# Fastino_DAC_channel.net
KiCad netlist of a schematic drawn in Altium Designer
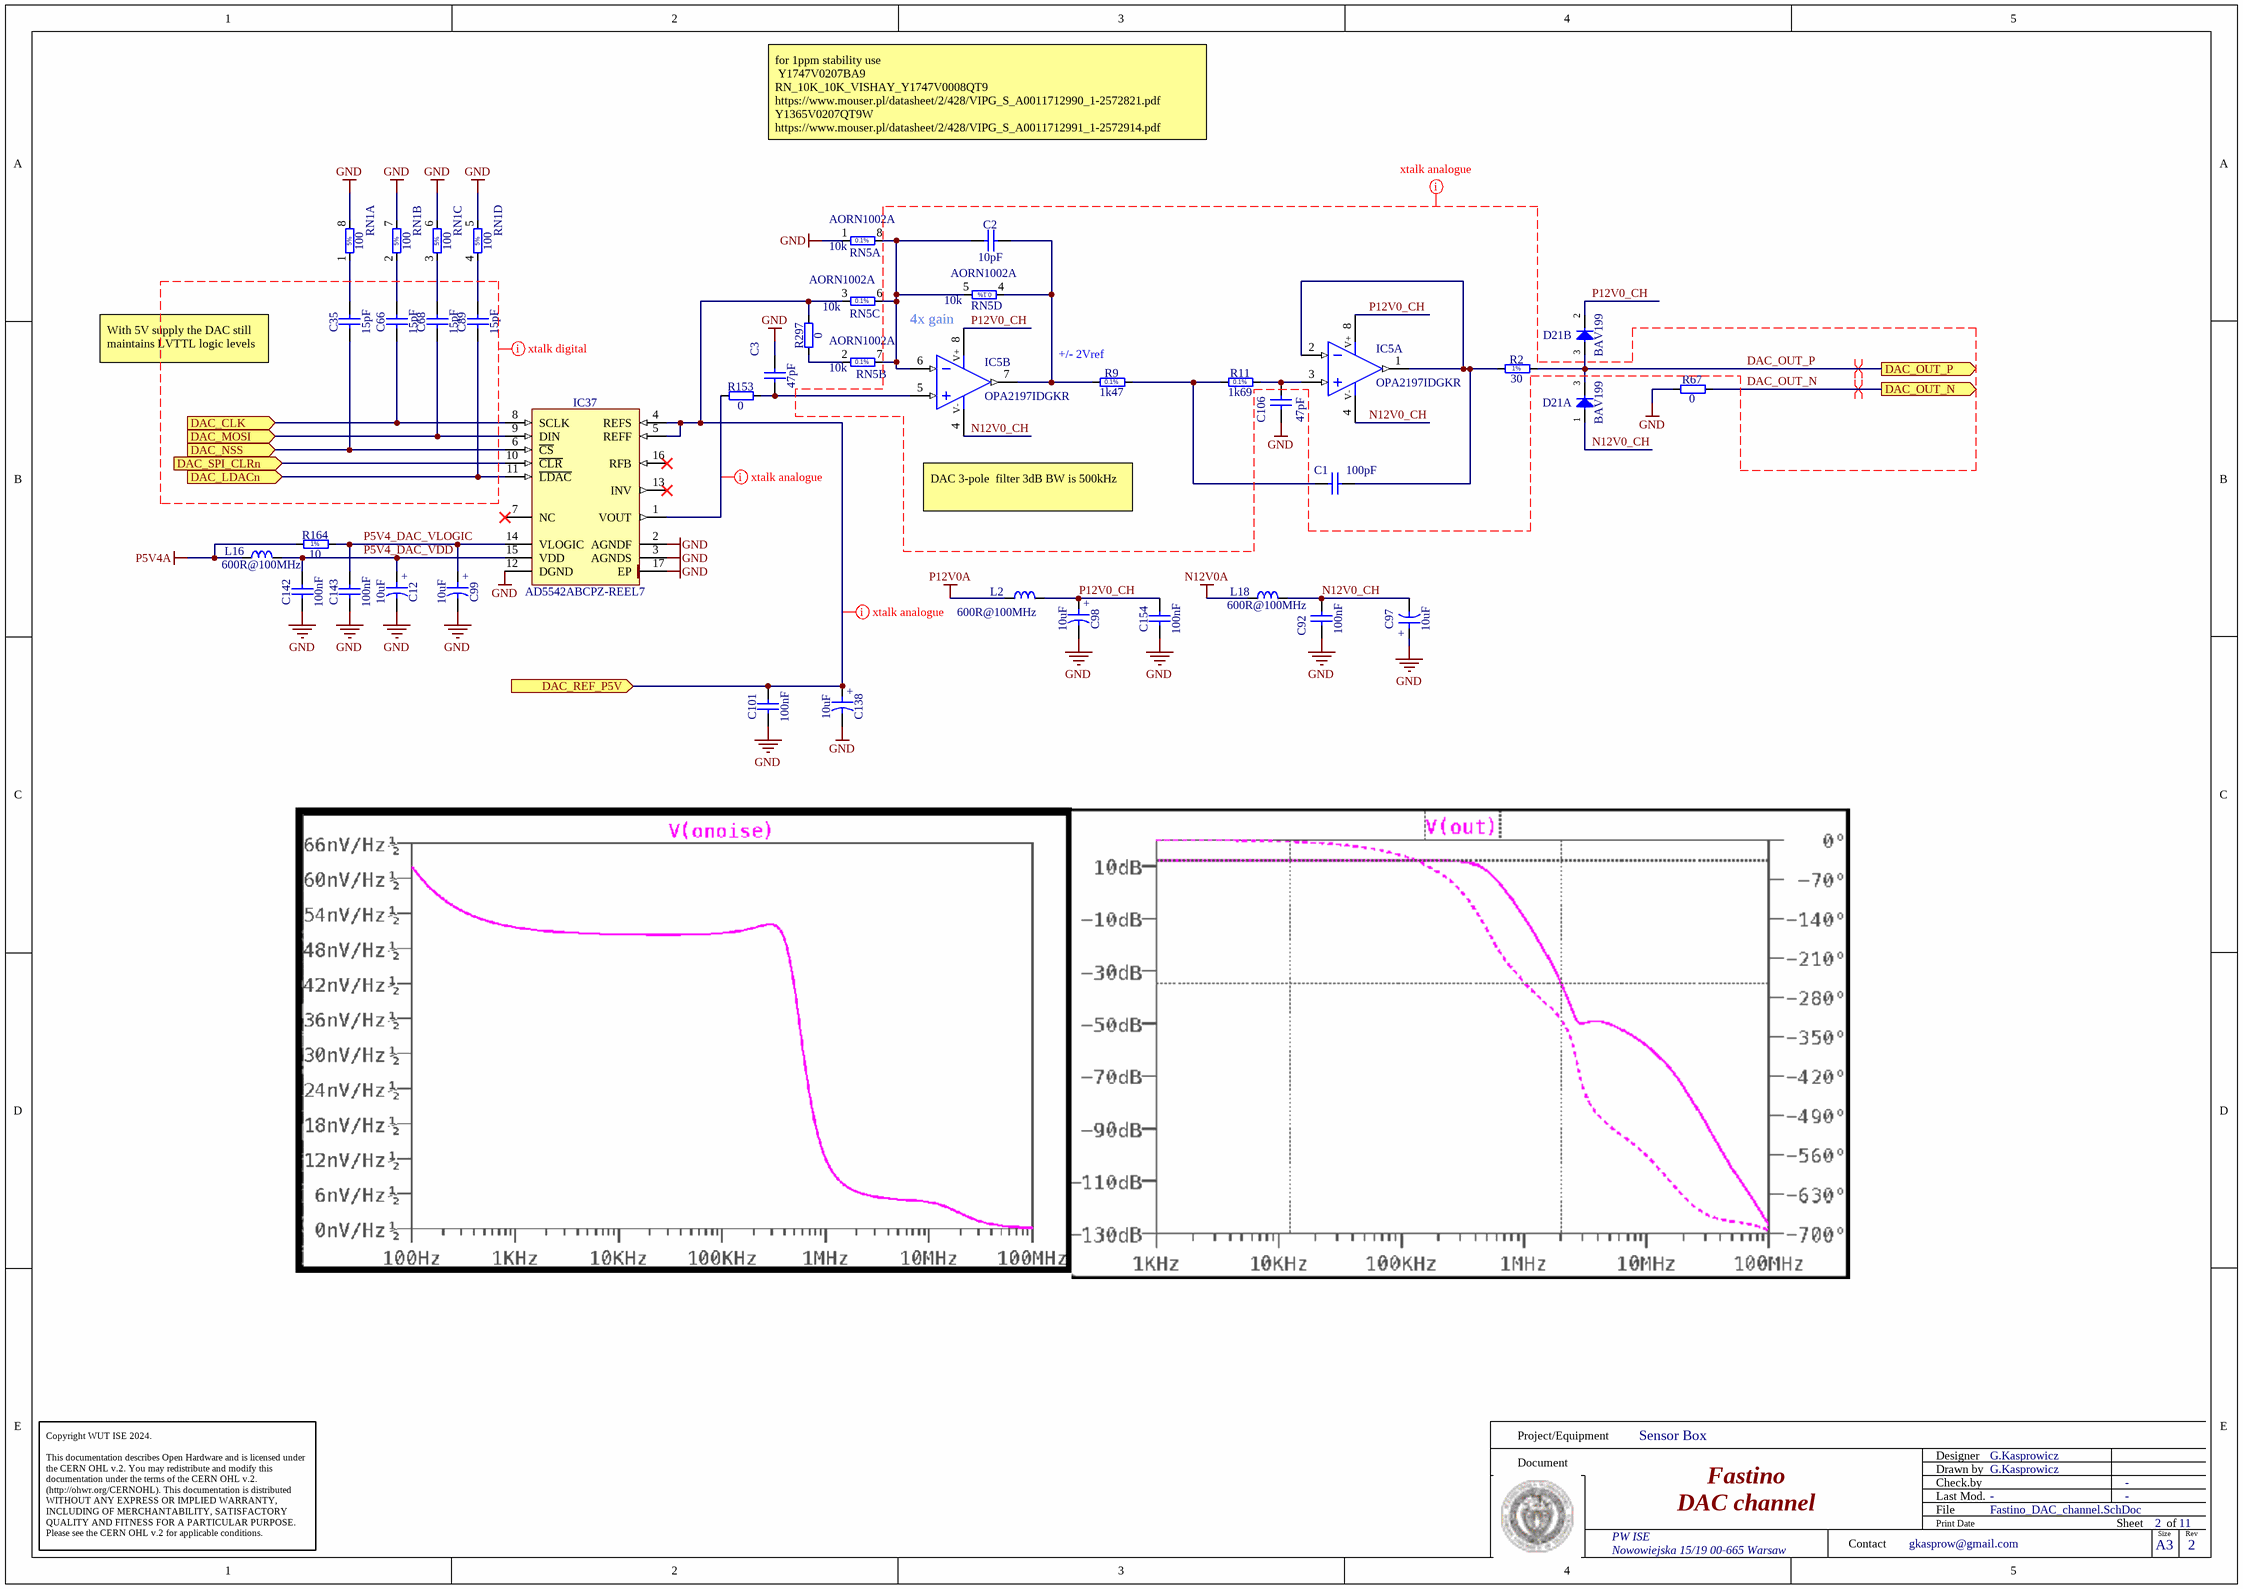
[diagram p0: Fastino_DAC_channel.SchDoc]

(export (version "E")
  (design (tool "Eeschema 10.0.6"))
  (components
    (comp (ref "C1")
      (value "100pF")
      (footprint "CAPC1608X90N")
      (description "Non-polarised capacitor")
      (fields
        (field (name "PART NUMBER") "CC0603_100PF_50V_1%_NP0")
        (field (name "VOLTAGE") "50V")
        (field (name "AUTHOR") "CERN DEM JLC")
      )
      (libsource (lib "Capacitors") (part "Capacitor - non polarized"))
    )
    (comp (ref "C2")
      (value "10pF")
      (footprint "CAPC1005X55N")
      (description "Non-polarised capacitor")
      (fields
        (field (name "PART NUMBER") "CC0402_10PF_50V_5%_C0G")
        (field (name "VOLTAGE") "50V")
        (field (name "AUTHOR") "CERN DEM JLC")
      )
      (libsource (lib "Capacitors") (part "Capacitor - non polarized"))
    )
    (comp (ref "C3")
      (value "47pF")
      (footprint "CAPC1005X55N")
      (description "Non-polarised capacitor")
      (fields
        (field (name "PART NUMBER") "CC0402_47PF_50V_1%_C0G_MURATA_GJM1555C1H470FB01D")
        (field (name "VOLTAGE") "50V")
        (field (name "AUTHOR") "CERN DEM BC")
      )
      (libsource (lib "Capacitors") (part "Capacitor - non polarized"))
    )
    (comp (ref "C12")
      (value "10uF")
      (footprint "CAPMP3216X180N")
      (description "Polarised capacitor")
      (fields
        (field (name "PART NUMBER") "CTE3216-18_10UF_16V_20%_AVX_TCJ")
        (field (name "VOLTAGE") "16V")
        (field (name "AUTHOR") "CERN DEM JLC")
      )
      (libsource (lib "Capacitors") (part "Capacitor - polarized"))
    )
    (comp (ref "C35")
      (value "15pF")
      (footprint "CAPC1608X87N")
      (description "Non-polarised capacitor")
      (fields
        (field (name "PART NUMBER") "CC0603_15PF_50V_5%_NP0")
        (field (name "VOLTAGE") "50V")
        (field (name "AUTHOR") "CERN DEM JLC")
      )
      (libsource (lib "Capacitors") (part "Capacitor - non polarized"))
    )
    (comp (ref "C66")
      (value "15pF")
      (footprint "CAPC1608X87N")
      (description "Non-polarised capacitor")
      (fields
        (field (name "PART NUMBER") "CC0603_15PF_50V_5%_NP0")
        (field (name "VOLTAGE") "50V")
        (field (name "AUTHOR") "CERN DEM JLC")
      )
      (libsource (lib "Capacitors") (part "Capacitor - non polarized"))
    )
    (comp (ref "C68")
      (value "15pF")
      (footprint "CAPC1608X87N")
      (description "Non-polarised capacitor")
      (fields
        (field (name "PART NUMBER") "CC0603_15PF_50V_5%_NP0")
        (field (name "VOLTAGE") "50V")
        (field (name "AUTHOR") "CERN DEM JLC")
      )
      (libsource (lib "Capacitors") (part "Capacitor - non polarized"))
    )
    (comp (ref "C89")
      (value "15pF")
      (footprint "CAPC1608X87N")
      (description "Non-polarised capacitor")
      (fields
        (field (name "PART NUMBER") "CC0603_15PF_50V_5%_NP0")
        (field (name "VOLTAGE") "50V")
        (field (name "AUTHOR") "CERN DEM JLC")
      )
      (libsource (lib "Capacitors") (part "Capacitor - non polarized"))
    )
    (comp (ref "C92")
      (value "100nF")
      (footprint "CAPC1005X55N")
      (description "Non-polarised capacitor")
      (fields
        (field (name "PART NUMBER") "CC0402_100NF_16V_10%_X7R")
        (field (name "VOLTAGE") "16V")
        (field (name "AUTHOR") "CERN DEM JLC")
      )
      (libsource (lib "Capacitors") (part "Capacitor - non polarized"))
    )
    (comp (ref "C97")
      (value "10uF")
      (footprint "CAPMP3216X180N")
      (description "Polarised capacitor")
      (fields
        (field (name "PART NUMBER") "CTE3216-18_10UF_16V_20%_AVX_TCJ")
        (field (name "VOLTAGE") "16V")
        (field (name "AUTHOR") "CERN DEM JLC")
      )
      (libsource (lib "Capacitors") (part "Capacitor - polarized"))
    )
    (comp (ref "C98")
      (value "10uF")
      (footprint "CAPMP3216X180N")
      (description "Polarised capacitor")
      (fields
        (field (name "PART NUMBER") "CTE3216-18_10UF_16V_20%_AVX_TCJ")
        (field (name "VOLTAGE") "16V")
        (field (name "AUTHOR") "CERN DEM JLC")
      )
      (libsource (lib "Capacitors") (part "Capacitor - polarized"))
    )
    (comp (ref "C99")
      (value "10uF")
      (footprint "CAPMP3216X180N")
      (description "Polarised capacitor")
      (fields
        (field (name "PART NUMBER") "CTE3216-18_10UF_16V_20%_AVX_TCJ")
        (field (name "VOLTAGE") "16V")
        (field (name "AUTHOR") "CERN DEM JLC")
      )
      (libsource (lib "Capacitors") (part "Capacitor - polarized"))
    )
    (comp (ref "C101")
      (value "100nF")
      (footprint "CAPC1005X55N")
      (description "Non-polarised capacitor")
      (fields
        (field (name "PART NUMBER") "CC0402_100NF_16V_10%_X7R")
        (field (name "VOLTAGE") "16V")
        (field (name "AUTHOR") "CERN DEM JLC")
      )
      (libsource (lib "Capacitors") (part "Capacitor - non polarized"))
    )
    (comp (ref "C106")
      (value "47pF")
      (footprint "CAPC1005X55N")
      (description "Non-polarised capacitor")
      (fields
        (field (name "PART NUMBER") "CC0402_47PF_50V_1%_C0G_MURATA_GJM1555C1H470FB01D")
        (field (name "VOLTAGE") "50V")
        (field (name "AUTHOR") "CERN DEM BC")
      )
      (libsource (lib "Capacitors") (part "Capacitor - non polarized"))
    )
    (comp (ref "C138")
      (value "10uF")
      (footprint "CAPMP3216X180N")
      (description "Polarised capacitor")
      (fields
        (field (name "PART NUMBER") "CTE3216-18_10UF_16V_20%_AVX_TCJ")
        (field (name "VOLTAGE") "16V")
        (field (name "AUTHOR") "CERN DEM JLC")
      )
      (libsource (lib "Capacitors") (part "Capacitor - polarized"))
    )
    (comp (ref "C142")
      (value "100nF")
      (footprint "CAPC1005X55N")
      (description "Non-polarised capacitor")
      (fields
        (field (name "PART NUMBER") "CC0402_100NF_16V_10%_X7R")
        (field (name "VOLTAGE") "16V")
        (field (name "AUTHOR") "CERN DEM JLC")
      )
      (libsource (lib "Capacitors") (part "Capacitor - non polarized"))
    )
    (comp (ref "C143")
      (value "100nF")
      (footprint "CAPC1005X55N")
      (description "Non-polarised capacitor")
      (fields
        (field (name "PART NUMBER") "CC0402_100NF_16V_10%_X7R")
        (field (name "VOLTAGE") "16V")
        (field (name "AUTHOR") "CERN DEM JLC")
      )
      (libsource (lib "Capacitors") (part "Capacitor - non polarized"))
    )
    (comp (ref "C154")
      (value "100nF")
      (footprint "CAPC1005X55N")
      (description "Non-polarised capacitor")
      (fields
        (field (name "PART NUMBER") "CC0402_100NF_16V_10%_X7R")
        (field (name "VOLTAGE") "16V")
        (field (name "AUTHOR") "CERN DEM JLC")
      )
      (libsource (lib "Capacitors") (part "Capacitor - non polarized"))
    )
    (comp (ref "D21")
      (value "BAV199")
      (footprint "SOT95P240X110-3N")
      (description "Serial Diode")
      (fields
        (field (name "VOLTAGE") "75V")
        (field (name "POWER") "250mW")
        (field (name "AUTHOR") "CERN DEM JMW")
      )
      (libsource (lib "ICs And Semiconductors") (part "Diode x2 A1C3_A3C2"))
    )
    (comp (ref "IC5")
      (value "OPA2197IDGKR")
      (footprint "SOP65P490X110-8N")
      (description "36-V, Precision, Rail-to-Rail Input Output, Low Offset Voltage Op Amp 8-VSSOP")
      (fields (field (name "MANUFACTURER") "TEXAS INSTRUMENTS") (field (name "AUTHOR") "GK"))
      (libsource (lib "ICs_Analog_Interfaces") (part "OA_OPA2197IDGKR"))
    )
    (comp (ref "IC37")
      (value "AD5542ABCPZ-REEL7")
      (footprint "QFN50P300X300X80-17N-S175")
      (description "2.7V to 5.5V, Serial-Input, Voltage-Output, 16-Bit DAC")
      (fields (field (name "MANUFACTURER") "ANALOG DEVICES") (field (name "AUTHOR") "CERN DEM JLC"))
      (libsource (lib "ICs And Semiconductors") (part "AD5542ABCPZ"))
    )
    (comp (ref "L2")
      (value "600R@100MHz")
      (footprint "INDC1005X55N")
      (description "Inductor")
      (fields
        (field (name "PART NUMBER") "IND0402_MURATA_BLM15HD601SN1")
        (field (name "POWER") "300mA")
        (field (name "AUTHOR") "CERN DEM JLC")
      )
      (libsource (lib "Inductors & Transformers") (part "Inductor"))
    )
    (comp (ref "L16")
      (value "600R@100MHz")
      (footprint "INDC1005X55N")
      (description "Inductor")
      (fields
        (field (name "PART NUMBER") "IND0402_MURATA_BLM15HD601SN1")
        (field (name "POWER") "300mA")
        (field (name "AUTHOR") "CERN DEM JLC")
      )
      (libsource (lib "Inductors & Transformers") (part "Inductor"))
    )
    (comp (ref "L18")
      (value "600R@100MHz")
      (footprint "INDC1005X55N")
      (description "Inductor")
      (fields
        (field (name "PART NUMBER") "IND0402_MURATA_BLM15HD601SN1")
        (field (name "POWER") "300mA")
        (field (name "AUTHOR") "CERN DEM JLC")
      )
      (libsource (lib "Inductors & Transformers") (part "Inductor"))
    )
    (comp (ref "R2")
      (value "30")
      (footprint "RESC1608X55N")
      (description "Resistor - 1%")
      (fields
        (field (name "PART NUMBER") "R0603_30R_1%_0.1W_100PPM")
        (field (name "POWER") "0.1W")
        (field (name "AUTHOR") "CERN DEM JLC")
      )
      (libsource (lib "Resistors") (part "Resistor - 1%"))
    )
    (comp (ref "R9")
      (value "1k47")
      (footprint "RESC1608X55N")
      (description "Resistor - 0.1%")
      (fields
        (field (name "PART NUMBER") "R0603_1K47_0.1%_0.063W_10PPM")
        (field (name "POWER") "0.063W")
        (field (name "AUTHOR") "CERN DEM JLC")
      )
      (libsource (lib "Resistors") (part "Resistor - 0.1%"))
    )
    (comp (ref "R11")
      (value "1k69")
      (footprint "RESC1608X55N")
      (description "Resistor - 0.1%")
      (fields
        (field (name "PART NUMBER") "R0603_1K69_0.1%_0.063W_10PPM")
        (field (name "POWER") "0.063W")
        (field (name "AUTHOR") "CERN DEM JLC")
      )
      (libsource (lib "Resistors") (part "Resistor - 0.1%"))
    )
    (comp (ref "R67")
      (value "0")
      (footprint "RESC1608X55N")
      (description "Resistor")
      (fields
        (field (name "PART NUMBER") "R0603_0R_JUMPER")
        (field (name "MANUFACTURER") "GENERIC")
        (field (name "AUTHOR") "CERN DEM JLC")
      )
      (libsource (lib "Resistors") (part "Resistor"))
    )
    (comp (ref "R153")
      (value "0")
      (footprint "RESC1005X40N")
      (description "Resistor")
      (fields
        (field (name "PART NUMBER") "R0402_0R_JUMPER")
        (field (name "MANUFACTURER") "GENERIC")
        (field (name "AUTHOR") "CERN DEM JLC")
      )
      (libsource (lib "Resistors") (part "Resistor"))
    )
    (comp (ref "R164")
      (value "10")
      (footprint "RESC1005X40N")
      (description "Resistor - 1%")
      (fields
        (field (name "PART NUMBER") "R0402_10R_1%_0.0625W_200PPM")
        (field (name "POWER") "0.0625W")
        (field (name "AUTHOR") "CERN DEM JLC")
      )
      (libsource (lib "Resistors") (part "Resistor - 1%"))
    )
    (comp (ref "R297")
      (value "0")
      (footprint "RESC0603X28N")
      (description "Resistor")
      (fields
        (field (name "PART NUMBER") "R0201_0R_JUMPER")
        (field (name "MANUFACTURER") "GENERIC")
        (field (name "AUTHOR") "CERN DEM JLC")
      )
      (libsource (lib "Resistors") (part "Resistor"))
    )
    (comp (ref "RN1")
      (value "100")
      (footprint "RN_YAGEO_TC124")
      (description "DIL8 Resistor Network 4 Isolated Resistor 5%")
      (fields
        (field (name "PART NUMBER") "RN_100R_YAGEO_TC124-JR-07100RL")
        (field (name "POWER") "0.062W")
        (field (name "AUTHOR") "CERN DEM BC")
      )
      (libsource (lib "Passives_RC") (part "RES_RN_100R_YAGEO_TC124-JR-07100RL"))
    )
    (comp (ref "RN5")
      (value "10k")
      (footprint "SOIC127P600X175-8N")
      (description "DIL8 Resistor Network 4 Isolated Resistor 0.1%")
      (fields
        (field (name "PART NUMBER") "RN_10K_VISHAY_AORN1002A")
        (field (name "POWER") "4x0.1W")
        (field (name "MANUFACTURER PART NUMBER") "AORN1002A")
        (field (name "AUTHOR") "CERN DEM JLC")
      )
      (libsource (lib "Resistors") (part "RN DIL8_4xR_Isolated_0.1%"))
    )
  )
  (nets
    (net (code "1") (name "/DAC_CLK") (class "Default")
      (node (ref "C66") (pin "1") (pinfunction "1_1") (pintype "passive"))
      (node (ref "IC37") (pin "8") (pinfunction "SCLK_8") (pintype "input"))
    )
    (net (code "2") (name "/DAC_LDACn") (class "Default")
      (node (ref "C89") (pin "1") (pinfunction "1_1") (pintype "passive"))
      (node (ref "IC37") (pin "11") (pinfunction "~{LDAC}_11") (pintype "input"))
    )
    (net (code "3") (name "/DAC_MOSI") (class "Default")
      (node (ref "C68") (pin "1") (pinfunction "1_1") (pintype "passive"))
      (node (ref "IC37") (pin "9") (pinfunction "DIN_9") (pintype "input"))
    )
    (net (code "4") (name "/DAC_NSS") (class "Default")
      (node (ref "C35") (pin "1") (pinfunction "1_1") (pintype "passive"))
      (node (ref "IC37") (pin "6") (pinfunction "~{CS}_6") (pintype "input"))
    )
    (net (code "5") (name "/DAC_OUT_N") (class "Default")
      (node (ref "R67") (pin "2") (pinfunction "2_2") (pintype "passive"))
    )
    (net (code "6") (name "/DAC_OUT_P") (class "Default")
      (node (ref "D21") (pin "3") (pinfunction "COMAC_3") (pintype "passive"))
      (node (ref "R2") (pin "2") (pinfunction "2_2") (pintype "passive"))
    )
    (net (code "7") (name "/DAC_REF_P5V") (class "Default")
      (node (ref "C101") (pin "2") (pinfunction "2_2") (pintype "passive"))
      (node (ref "C138") (pin "1") (pinfunction "1_1") (pintype "passive"))
      (node (ref "IC37") (pin "4") (pinfunction "REFS_4") (pintype "input"))
      (node (ref "IC37") (pin "5") (pinfunction "REFF_5") (pintype "input"))
      (node (ref "R297") (pin "2") (pinfunction "2_2") (pintype "passive"))
      (node (ref "RN5") (pin "3") (pinfunction "3_3") (pintype "passive"))
    )
    (net (code "8") (name "/DAC_SPI_CLRn") (class "Default")
      (node (ref "IC37") (pin "10") (pinfunction "~{CLR}_10") (pintype "input"))
    )
    (net (code "9") (name "/N12V0_CH") (class "Default")
      (node (ref "C92") (pin "2") (pinfunction "2_2") (pintype "passive"))
      (node (ref "C97") (pin "2") (pinfunction "2_2") (pintype "passive"))
      (node (ref "D21") (pin "1") (pinfunction "A_1") (pintype "passive"))
      (node (ref "IC5") (pin "4") (pinfunction "V-_4") (pintype "power_in"))
      (node (ref "L18") (pin "2") (pinfunction "2_2") (pintype "passive"))
    )
    (net (code "10") (name "/P5V4_DAC_VDD") (class "Default")
      (node (ref "C12") (pin "1") (pinfunction "1_1") (pintype "passive"))
      (node (ref "C142") (pin "2") (pinfunction "2_2") (pintype "passive"))
      (node (ref "IC37") (pin "15") (pinfunction "VDD_15") (pintype "power_in"))
      (node (ref "L16") (pin "2") (pinfunction "2_2") (pintype "passive"))
    )
    (net (code "11") (name "/P5V4_DAC_VLOGIC") (class "Default")
      (node (ref "C143") (pin "2") (pinfunction "2_2") (pintype "passive"))
      (node (ref "C99") (pin "1") (pinfunction "1_1") (pintype "passive"))
      (node (ref "IC37") (pin "14") (pinfunction "VLOGIC_14") (pintype "power_in"))
      (node (ref "R164") (pin "2") (pinfunction "2_2") (pintype "passive"))
    )
    (net (code "12") (name "/P12V0_CH") (class "Default")
      (node (ref "C154") (pin "2") (pinfunction "2_2") (pintype "passive"))
      (node (ref "C98") (pin "1") (pinfunction "1_1") (pintype "passive"))
      (node (ref "D21") (pin "2") (pinfunction "C_2") (pintype "passive"))
      (node (ref "IC5") (pin "8") (pinfunction "V+_8") (pintype "power_in"))
      (node (ref "L2") (pin "2") (pinfunction "2_2") (pintype "passive"))
    )
    (net (code "13") (name "GND") (class "Default")
      (node (ref "C101") (pin "1") (pinfunction "1_1") (pintype "passive"))
      (node (ref "C106") (pin "1") (pinfunction "1_1") (pintype "passive"))
      (node (ref "C12") (pin "2") (pinfunction "2_2") (pintype "passive"))
      (node (ref "C138") (pin "2") (pinfunction "2_2") (pintype "passive"))
      (node (ref "C142") (pin "1") (pinfunction "1_1") (pintype "passive"))
      (node (ref "C143") (pin "1") (pinfunction "1_1") (pintype "passive"))
      (node (ref "C154") (pin "1") (pinfunction "1_1") (pintype "passive"))
      (node (ref "C3") (pin "2") (pinfunction "2_2") (pintype "passive"))
      (node (ref "C92") (pin "1") (pinfunction "1_1") (pintype "passive"))
      (node (ref "C97") (pin "1") (pinfunction "1_1") (pintype "passive"))
      (node (ref "C98") (pin "2") (pinfunction "2_2") (pintype "passive"))
      (node (ref "C99") (pin "2") (pinfunction "2_2") (pintype "passive"))
      (node (ref "IC37") (pin "12") (pinfunction "DGND_12") (pintype "power_in"))
      (node (ref "IC37") (pin "17") (pinfunction "EP_17") (pintype "power_in"))
      (node (ref "IC37") (pin "2") (pinfunction "AGNDF_2") (pintype "power_in"))
      (node (ref "IC37") (pin "3") (pinfunction "AGNDS_3") (pintype "power_in"))
      (node (ref "R67") (pin "1") (pinfunction "1_1") (pintype "passive"))
      (node (ref "RN1") (pin "5") (pinfunction "5_5") (pintype "passive"))
      (node (ref "RN1") (pin "6") (pinfunction "6_6") (pintype "passive"))
      (node (ref "RN1") (pin "7") (pinfunction "7_7") (pintype "passive"))
      (node (ref "RN1") (pin "8") (pinfunction "8_8") (pintype "passive"))
      (node (ref "RN5") (pin "1") (pinfunction "1_1") (pintype "passive"))
    )
    (net (code "14") (name "N12V0A") (class "Default")
      (node (ref "L18") (pin "1") (pinfunction "1_1") (pintype "passive"))
    )
    (net (code "15") (name "Net-(C1-Pad2)") (class "Default")
      (node (ref "C1") (pin "2") (pinfunction "2_2") (pintype "passive"))
      (node (ref "R11") (pin "1") (pinfunction "1_1") (pintype "passive"))
      (node (ref "R9") (pin "2") (pinfunction "2_2") (pintype "passive"))
    )
    (net (code "16") (name "Net-(C35-Pad2)") (class "Default")
      (node (ref "C35") (pin "2") (pinfunction "2_2") (pintype "passive"))
      (node (ref "RN1") (pin "1") (pinfunction "1_1") (pintype "passive"))
    )
    (net (code "17") (name "Net-(C66-Pad2)") (class "Default")
      (node (ref "C66") (pin "2") (pinfunction "2_2") (pintype "passive"))
      (node (ref "RN1") (pin "2") (pinfunction "2_2") (pintype "passive"))
    )
    (net (code "18") (name "Net-(C68-Pad2)") (class "Default")
      (node (ref "C68") (pin "2") (pinfunction "2_2") (pintype "passive"))
      (node (ref "RN1") (pin "3") (pinfunction "3_3") (pintype "passive"))
    )
    (net (code "19") (name "Net-(C89-Pad2)") (class "Default")
      (node (ref "C89") (pin "2") (pinfunction "2_2") (pintype "passive"))
      (node (ref "RN1") (pin "4") (pinfunction "4_4") (pintype "passive"))
    )
    (net (code "20") (name "Net-(IC5A-IN+)") (class "Default")
      (node (ref "C106") (pin "2") (pinfunction "2_2") (pintype "passive"))
      (node (ref "IC5") (pin "3") (pinfunction "IN+_3") (pintype "input"))
      (node (ref "R11") (pin "2") (pinfunction "2_2") (pintype "passive"))
    )
    (net (code "21") (name "Net-(IC5A-IN-)") (class "Default")
      (node (ref "C1") (pin "1") (pinfunction "1_1") (pintype "passive"))
      (node (ref "IC5") (pin "1") (pinfunction "OUT_1") (pintype "output"))
      (node (ref "IC5") (pin "2") (pinfunction "IN-_2") (pintype "input"))
      (node (ref "R2") (pin "1") (pinfunction "1_1") (pintype "passive"))
    )
    (net (code "22") (name "Net-(IC5B-IN+)") (class "Default")
      (node (ref "C3") (pin "1") (pinfunction "1_1") (pintype "passive"))
      (node (ref "IC5") (pin "5") (pinfunction "IN+_5") (pintype "input"))
      (node (ref "R153") (pin "2") (pinfunction "2_2") (pintype "passive"))
    )
    (net (code "23") (name "Net-(IC5B-IN-)") (class "Default")
      (node (ref "C2") (pin "1") (pinfunction "1_1") (pintype "passive"))
      (node (ref "IC5") (pin "6") (pinfunction "IN-_6") (pintype "input"))
      (node (ref "RN5") (pin "5") (pinfunction "5_5") (pintype "passive"))
      (node (ref "RN5") (pin "6") (pinfunction "6_6") (pintype "passive"))
      (node (ref "RN5") (pin "7") (pinfunction "7_7") (pintype "passive"))
      (node (ref "RN5") (pin "8") (pinfunction "8_8") (pintype "passive"))
    )
    (net (code "24") (name "Net-(IC5B-OUT)") (class "Default")
      (node (ref "C2") (pin "2") (pinfunction "2_2") (pintype "passive"))
      (node (ref "IC5") (pin "7") (pinfunction "OUT_7") (pintype "output"))
      (node (ref "R9") (pin "1") (pinfunction "1_1") (pintype "passive"))
      (node (ref "RN5") (pin "4") (pinfunction "4_4") (pintype "passive"))
    )
    (net (code "25") (name "Net-(IC37-VOUT)") (class "Default")
      (node (ref "IC37") (pin "1") (pinfunction "VOUT_1") (pintype "output"))
      (node (ref "R153") (pin "1") (pinfunction "1_1") (pintype "passive"))
    )
    (net (code "26") (name "Net-(R297-Pad1)") (class "Default")
      (node (ref "R297") (pin "1") (pinfunction "1_1") (pintype "passive"))
      (node (ref "RN5") (pin "2") (pinfunction "2_2") (pintype "passive"))
    )
    (net (code "27") (name "P5V4A") (class "Default")
      (node (ref "L16") (pin "1") (pinfunction "1_1") (pintype "passive"))
      (node (ref "R164") (pin "1") (pinfunction "1_1") (pintype "passive"))
    )
    (net (code "28") (name "P12V0A") (class "Default")
      (node (ref "L2") (pin "1") (pinfunction "1_1") (pintype "passive"))
    )
    (net (code "29") (name "unconnected-(IC37-INV-Pad13)") (class "Default")
      (node (ref "IC37") (pin "13") (pinfunction "INV_13") (pintype "output+no_connect"))
    )
    (net (code "30") (name "unconnected-(IC37-NC-Pad7)") (class "Default")
      (node (ref "IC37") (pin "7") (pinfunction "NC_7") (pintype "passive+no_connect"))
    )
    (net (code "31") (name "unconnected-(IC37-RFB-Pad16)") (class "Default")
      (node (ref "IC37") (pin "16") (pinfunction "RFB_16") (pintype "input+no_connect"))
    )
  )
)
